# OBD2.net
KiCad netlist of a schematic drawn in Altium Designer
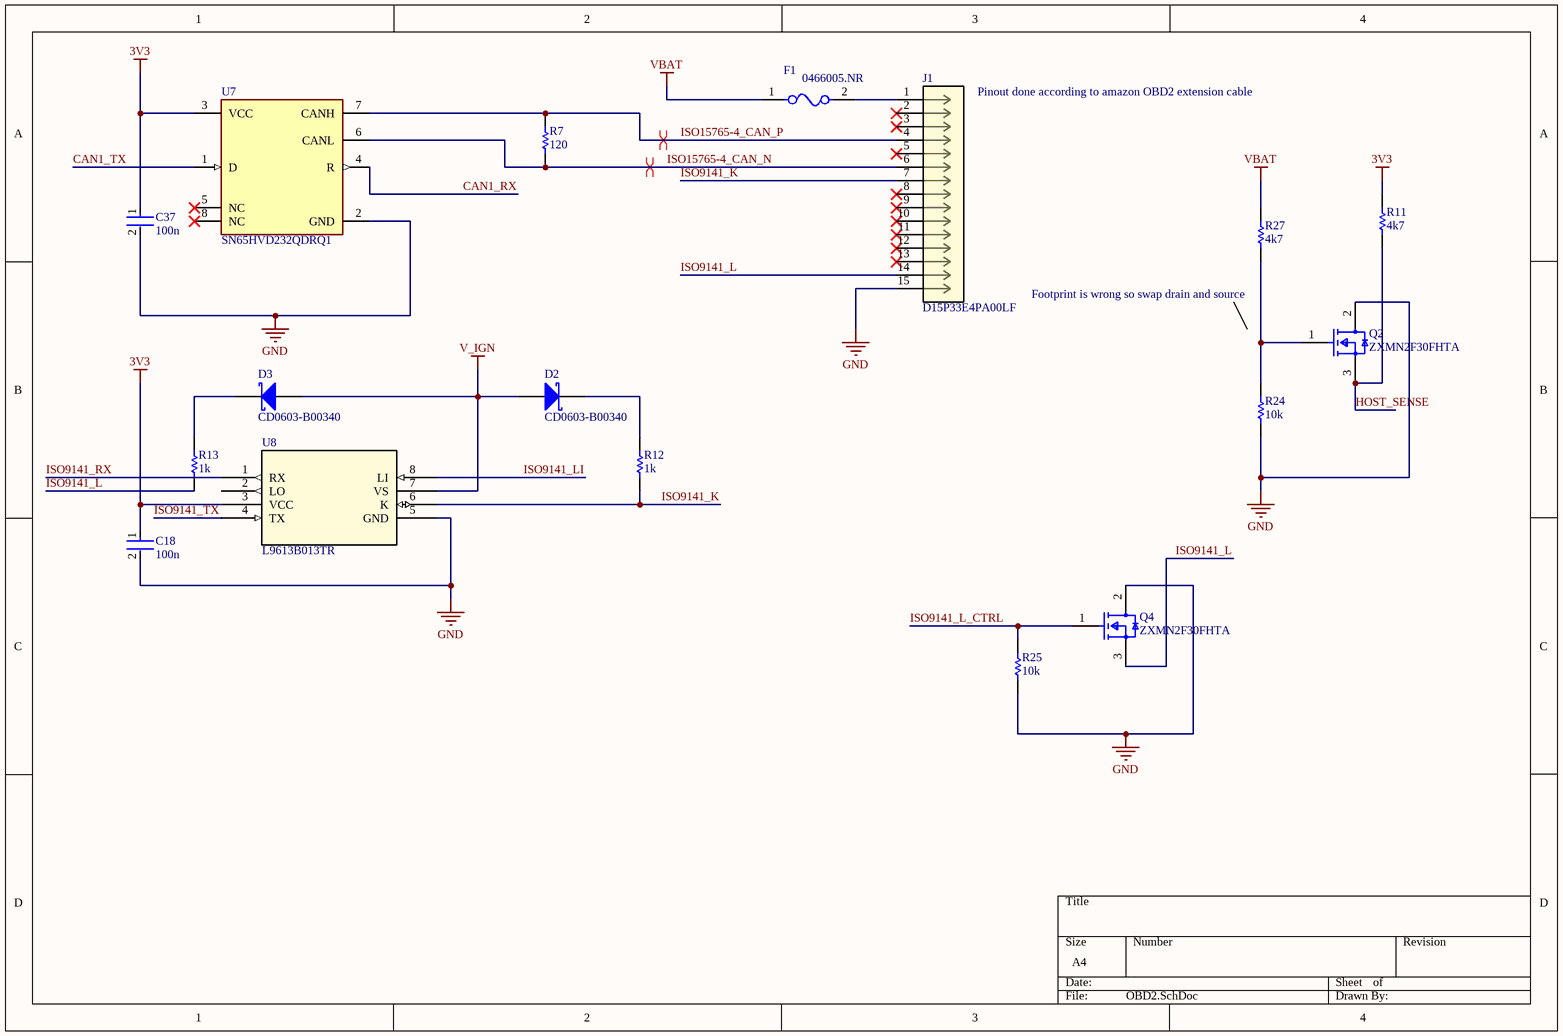
[diagram p0: OBD2.SchDoc]

(export (version "E")
  (design (tool "Eeschema 10.0.6"))
  (components
    (comp (ref "C18")
      (value "100n")
      (footprint "FP-GRM188-0_1-e0_2_0_55-IPC_A")
      (description "Chip Multilayer Ceramic Capacitors for General Purpose, 0603, 10uF, X5R, 15%, 20%, 6.3V")
      (fields (field (name "VOLTAGE") "6.3V") (field (name "TOLERANCE") "20%"))
      (libsource (lib "Altium Content Vault") (part "02cd4be3c70576c341d710602a673aa"))
    )
    (comp (ref "C37")
      (value "100n")
      (footprint "FP-GRM188-0_1-e0_2_0_55-IPC_A")
      (description "Chip Multilayer Ceramic Capacitors for General Purpose, 0603, 10uF, X5R, 15%, 20%, 6.3V")
      (fields (field (name "VOLTAGE") "6.3V") (field (name "TOLERANCE") "20%"))
      (libsource (lib "Altium Content Vault") (part "02cd4be3c70576c341d710602a673aa"))
    )
    (comp (ref "D2")
      (value "CD0603-B00340")
      (footprint "BOUR-0603_V")
      (fields (field (name "MANUFACTURER") "Bourns"))
      (libsource (lib "Altium Content Vault") (part "DSKY-AK-2"))
    )
    (comp (ref "D3")
      (value "CD0603-B00340")
      (footprint "BOUR-0603_V")
      (fields (field (name "MANUFACTURER") "Bourns"))
      (libsource (lib "Altium Content Vault") (part "DSKY-AK-2"))
    )
    (comp (ref "F1")
      (value "0466005.NR")
      (footprint "FP-0466-MFG")
      (description "FUSE BOARD MNT 5A 32VAC/VDC 1206")
      (fields
        (field (name "OCTOPART") "https://octopart.com/0466005.nr-littelfuse-143206")
        (field (name "MANUFACTURER") "Littelfuse Inc")
      )
      (libsource (lib "Altium Content Vault") (part "5bcf9b9f640e542cf0359d10258e979"))
    )
    (comp (ref "J1")
      (value "D15P33E4PA00LF")
      (footprint "CONN9_LD15P_1556x500_AMP")
      (description "No Description Available")
      (libsource (lib "Master") (part "D15P33E4PA00LF"))
    )
    (comp (ref "Q2")
      (value "ZXMN2F30FHTA")
      (footprint "FP-SOT23-IPC_C")
      (description "MOSFET N-CH 20V 4.1A SOT23-3")
      (libsource (lib "Altium Content Vault") (part "81f72b6ee68bbac5d432bdb9a440643"))
    )
    (comp (ref "Q4")
      (value "ZXMN2F30FHTA")
      (footprint "FP-SOT23-IPC_C")
      (description "MOSFET N-CH 20V 4.1A SOT23-3")
      (libsource (lib "Altium Content Vault") (part "81f72b6ee68bbac5d432bdb9a440643"))
    )
    (comp (ref "R7")
      (value "120")
      (footprint "RESC1608X55X30ML15T15")
      (fields (field (name "PART NUMBER") "ERJ-3EKF1003V") (field (name "MANUFACTURER") "Panasonic"))
      (libsource (lib "Altium Content Vault") (part "RES"))
    )
    (comp (ref "R11")
      (value "4k7")
      (footprint "RESC1608X55X30ML15T15")
      (fields (field (name "PART NUMBER") "ERJ-3EKF1003V") (field (name "MANUFACTURER") "Panasonic"))
      (libsource (lib "Altium Content Vault") (part "RES"))
    )
    (comp (ref "R12")
      (value "1k")
      (footprint "RESC1608X55X30ML15T15")
      (fields (field (name "PART NUMBER") "ERJ-3EKF1003V") (field (name "MANUFACTURER") "Panasonic"))
      (libsource (lib "Altium Content Vault") (part "RES"))
    )
    (comp (ref "R13")
      (value "1k")
      (footprint "RESC1608X55X30ML15T15")
      (fields (field (name "PART NUMBER") "ERJ-3EKF1003V") (field (name "MANUFACTURER") "Panasonic"))
      (libsource (lib "Altium Content Vault") (part "RES"))
    )
    (comp (ref "R24")
      (value "10k")
      (footprint "RESC1608X55X30ML15T15")
      (fields (field (name "PART NUMBER") "ERJ-3EKF1003V") (field (name "MANUFACTURER") "Panasonic"))
      (libsource (lib "Altium Content Vault") (part "RES"))
    )
    (comp (ref "R25")
      (value "10k")
      (footprint "RESC1608X55X30ML15T15")
      (fields (field (name "PART NUMBER") "ERJ-3EKF1003V") (field (name "MANUFACTURER") "Panasonic"))
      (libsource (lib "Altium Content Vault") (part "RES"))
    )
    (comp (ref "R27")
      (value "4k7")
      (footprint "RESC1608X55X30ML15T15")
      (fields (field (name "PART NUMBER") "ERJ-3EKF1003V") (field (name "MANUFACTURER") "Panasonic"))
      (libsource (lib "Altium Content Vault") (part "RES"))
    )
    (comp (ref "U7")
      (value "SN65HVD232QDRQ1")
      (footprint "FP-D0008A-MFG")
      (description "IC TRANSCEIVER HALF 1/1 8SOIC")
      (libsource (lib "Altium Content Vault") (part "3bf20a45497b8b0096c58641b0f280c"))
    )
    (comp (ref "U8")
      (value "L9613B013TR")
      (footprint "L9613B013TR_STM")
      (description "No Description Available")
      (libsource (lib "Master") (part "L9613B013TR"))
    )
  )
  (nets
    (net (code "1") (name "/CAN1_RX") (class "Default")
      (node (ref "U7") (pin "4") (pinfunction "R_4") (pintype "output"))
    )
    (net (code "2") (name "/CAN1_TX") (class "Default")
      (node (ref "U7") (pin "1") (pinfunction "D_1") (pintype "input"))
    )
    (net (code "3") (name "/HOST_SENSE") (class "Default")
      (node (ref "Q2") (pin "3") (pinfunction "D_3") (pintype "passive"))
      (node (ref "R11") (pin "1") (pinfunction "1_1") (pintype "passive"))
    )
    (net (code "4") (name "/ISO9141_K") (class "Default")
      (node (ref "J1") (pin "7") (pinfunction "7_7") (pintype "passive"))
      (node (ref "R12") (pin "1") (pinfunction "1_1") (pintype "passive"))
      (node (ref "U8") (pin "6") (pinfunction "K_6") (pintype "bidirectional"))
    )
    (net (code "5") (name "/ISO9141_L") (class "Default")
      (node (ref "J1") (pin "14") (pinfunction "14_14") (pintype "passive"))
      (node (ref "Q4") (pin "3") (pinfunction "D_3") (pintype "passive"))
      (node (ref "R13") (pin "1") (pinfunction "1_1") (pintype "passive"))
    )
    (net (code "6") (name "/ISO9141_LI") (class "Default")
      (node (ref "U8") (pin "8") (pinfunction "LI_8") (pintype "input"))
    )
    (net (code "7") (name "/ISO9141_L_CTRL") (class "Default")
      (node (ref "Q4") (pin "1") (pinfunction "G_1") (pintype "passive"))
      (node (ref "R25") (pin "2") (pinfunction "2_2") (pintype "passive"))
    )
    (net (code "8") (name "/ISO9141_RX") (class "Default")
      (node (ref "U8") (pin "1") (pinfunction "RX_1") (pintype "output"))
    )
    (net (code "9") (name "/ISO9141_TX") (class "Default")
      (node (ref "U8") (pin "4") (pinfunction "TX_4") (pintype "input"))
    )
    (net (code "10") (name "/ISO15765-4_CAN_N") (class "Default")
      (node (ref "J1") (pin "6") (pinfunction "6_6") (pintype "passive"))
      (node (ref "R7") (pin "1") (pinfunction "1_1") (pintype "passive"))
      (node (ref "U7") (pin "6") (pinfunction "CANL_6") (pintype "passive"))
    )
    (net (code "11") (name "/ISO15765-4_CAN_P") (class "Default")
      (node (ref "J1") (pin "4") (pinfunction "4_4") (pintype "passive"))
      (node (ref "R7") (pin "2") (pinfunction "2_2") (pintype "passive"))
      (node (ref "U7") (pin "7") (pinfunction "CANH_7") (pintype "passive"))
    )
    (net (code "12") (name "3V3") (class "Default")
      (node (ref "C18") (pin "1") (pinfunction "1_1") (pintype "passive"))
      (node (ref "C37") (pin "1") (pinfunction "1_1") (pintype "passive"))
      (node (ref "R11") (pin "2") (pinfunction "2_2") (pintype "passive"))
      (node (ref "U7") (pin "3") (pinfunction "VCC_3") (pintype "power_in"))
      (node (ref "U8") (pin "3") (pinfunction "VCC_3") (pintype "power_in"))
    )
    (net (code "13") (name "GND") (class "Default")
      (node (ref "C18") (pin "2") (pinfunction "2_2") (pintype "passive"))
      (node (ref "C37") (pin "2") (pinfunction "2_2") (pintype "passive"))
      (node (ref "J1") (pin "15") (pinfunction "15_15") (pintype "passive"))
      (node (ref "Q2") (pin "2") (pinfunction "S_2") (pintype "passive"))
      (node (ref "Q4") (pin "2") (pinfunction "S_2") (pintype "passive"))
      (node (ref "R24") (pin "1") (pinfunction "1_1") (pintype "passive"))
      (node (ref "R25") (pin "1") (pinfunction "1_1") (pintype "passive"))
      (node (ref "U7") (pin "2") (pinfunction "GND_2") (pintype "power_in"))
      (node (ref "U8") (pin "5") (pinfunction "GND_5") (pintype "power_in"))
    )
    (net (code "14") (name "Net-(D2-K)") (class "Default")
      (node (ref "D2") (pin "2") (pinfunction "K_2") (pintype "passive"))
      (node (ref "R12") (pin "2") (pinfunction "2_2") (pintype "passive"))
    )
    (net (code "15") (name "Net-(D3-K)") (class "Default")
      (node (ref "D3") (pin "2") (pinfunction "K_2") (pintype "passive"))
      (node (ref "R13") (pin "2") (pinfunction "2_2") (pintype "passive"))
    )
    (net (code "16") (name "Net-(F1-Pad2)") (class "Default")
      (node (ref "F1") (pin "2") (pinfunction "2_2") (pintype "passive"))
      (node (ref "J1") (pin "1") (pinfunction "1_1") (pintype "passive"))
    )
    (net (code "17") (name "Net-(Q2-G)") (class "Default")
      (node (ref "Q2") (pin "1") (pinfunction "G_1") (pintype "passive"))
      (node (ref "R24") (pin "2") (pinfunction "2_2") (pintype "passive"))
      (node (ref "R27") (pin "1") (pinfunction "1_1") (pintype "passive"))
    )
    (net (code "18") (name "VBAT") (class "Default")
      (node (ref "F1") (pin "1") (pinfunction "1_1") (pintype "passive"))
      (node (ref "R27") (pin "2") (pinfunction "2_2") (pintype "passive"))
    )
    (net (code "19") (name "V_IGN") (class "Default")
      (node (ref "D2") (pin "1") (pinfunction "A_1") (pintype "passive"))
      (node (ref "D3") (pin "1") (pinfunction "A_1") (pintype "passive"))
      (node (ref "U8") (pin "7") (pinfunction "VS_7") (pintype "power_in"))
    )
    (net (code "20") (name "unconnected-(J1-Pad2)") (class "Default")
      (node (ref "J1") (pin "2") (pinfunction "2_2") (pintype "passive+no_connect"))
    )
    (net (code "21") (name "unconnected-(J1-Pad3)") (class "Default")
      (node (ref "J1") (pin "3") (pinfunction "3_3") (pintype "passive+no_connect"))
    )
    (net (code "22") (name "unconnected-(J1-Pad5)") (class "Default")
      (node (ref "J1") (pin "5") (pinfunction "5_5") (pintype "passive+no_connect"))
    )
    (net (code "23") (name "unconnected-(J1-Pad8)") (class "Default")
      (node (ref "J1") (pin "8") (pinfunction "8_8") (pintype "passive+no_connect"))
    )
    (net (code "24") (name "unconnected-(J1-Pad9)") (class "Default")
      (node (ref "J1") (pin "9") (pinfunction "9_9") (pintype "passive+no_connect"))
    )
    (net (code "25") (name "unconnected-(J1-Pad10)") (class "Default")
      (node (ref "J1") (pin "10") (pinfunction "10_10") (pintype "passive+no_connect"))
    )
    (net (code "26") (name "unconnected-(J1-Pad11)") (class "Default")
      (node (ref "J1") (pin "11") (pinfunction "11_11") (pintype "passive+no_connect"))
    )
    (net (code "27") (name "unconnected-(J1-Pad12)") (class "Default")
      (node (ref "J1") (pin "12") (pinfunction "12_12") (pintype "passive+no_connect"))
    )
    (net (code "28") (name "unconnected-(J1-Pad13)") (class "Default")
      (node (ref "J1") (pin "13") (pinfunction "13_13") (pintype "passive+no_connect"))
    )
    (net (code "29") (name "unconnected-(U7-NC-Pad5)") (class "Default")
      (node (ref "U7") (pin "5") (pinfunction "NC_5") (pintype "passive+no_connect"))
    )
    (net (code "30") (name "unconnected-(U7-NC-Pad8)") (class "Default")
      (node (ref "U7") (pin "8") (pinfunction "NC_8") (pintype "passive+no_connect"))
    )
    (net (code "31") (name "unconnected-(U8-LO-Pad2)") (class "Default")
      (node (ref "U8") (pin "2") (pinfunction "LO_2") (pintype "output"))
    )
  )
)
